# sensor.net
KiCad netlist of a schematic drawn in EAGLE
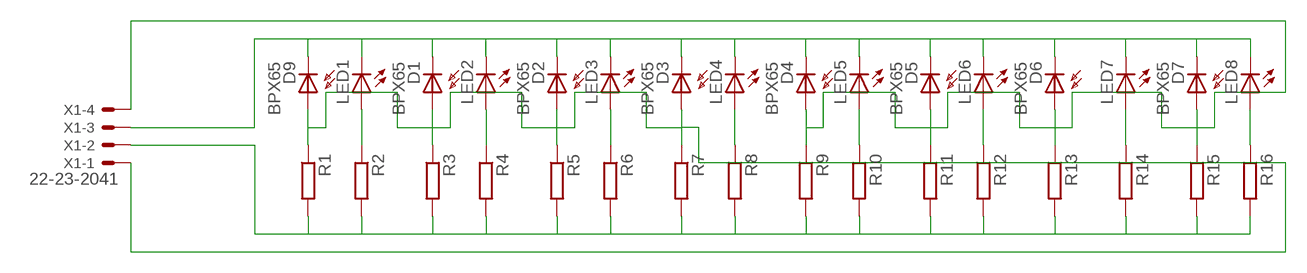
[diagram p0: schematic, sheet 1]

(export (version "E")
  (design (tool "Eeschema 10.0.6"))
  (components
    (comp (ref "D1")
      (value "BPX65")
      (footprint "eagle-import:BPX65")
      (fields
        (field (name "MPN") "BPX65.")
        (field (name "MPN_1") "BPX65.")
        (field (name "OC_FARNELL") "327451")
        (field (name "OC_NEWARK") "06WX2764")
      )
      (libsource (lib "eagle-import") (part "BPX65"))
    )
    (comp (ref "D2")
      (value "BPX65")
      (footprint "eagle-import:BPX65")
      (fields
        (field (name "MPN") "BPX65.")
        (field (name "MPN_1") "BPX65.")
        (field (name "OC_FARNELL") "327451")
        (field (name "OC_NEWARK") "06WX2764")
      )
      (libsource (lib "eagle-import") (part "BPX65"))
    )
    (comp (ref "D3")
      (value "BPX65")
      (footprint "eagle-import:BPX65")
      (fields
        (field (name "MPN") "BPX65.")
        (field (name "MPN_1") "BPX65.")
        (field (name "OC_FARNELL") "327451")
        (field (name "OC_NEWARK") "06WX2764")
      )
      (libsource (lib "eagle-import") (part "BPX65"))
    )
    (comp (ref "D4")
      (value "BPX65")
      (footprint "eagle-import:BPX65")
      (fields
        (field (name "MPN") "BPX65.")
        (field (name "MPN_1") "BPX65.")
        (field (name "OC_FARNELL") "327451")
        (field (name "OC_NEWARK") "06WX2764")
      )
      (libsource (lib "eagle-import") (part "BPX65"))
    )
    (comp (ref "D5")
      (value "BPX65")
      (footprint "eagle-import:BPX65")
      (fields
        (field (name "MPN") "BPX65.")
        (field (name "MPN_1") "BPX65.")
        (field (name "OC_FARNELL") "327451")
        (field (name "OC_NEWARK") "06WX2764")
      )
      (libsource (lib "eagle-import") (part "BPX65"))
    )
    (comp (ref "D6")
      (value "BPX65")
      (footprint "eagle-import:BPX65")
      (fields
        (field (name "MPN") "BPX65.")
        (field (name "MPN_1") "BPX65.")
        (field (name "OC_FARNELL") "327451")
        (field (name "OC_NEWARK") "06WX2764")
      )
      (libsource (lib "eagle-import") (part "BPX65"))
    )
    (comp (ref "D7")
      (value "BPX65")
      (footprint "eagle-import:BPX65")
      (fields
        (field (name "MPN") "BPX65.")
        (field (name "MPN_1") "BPX65.")
        (field (name "OC_FARNELL") "327451")
        (field (name "OC_NEWARK") "06WX2764")
      )
      (libsource (lib "eagle-import") (part "BPX65"))
    )
    (comp (ref "D9")
      (value "BPX65")
      (footprint "eagle-import:BPX65")
      (fields (field (name "MPN") "BPX65."))
      (libsource (lib "eagle-import") (part "BPX65"))
    )
    (comp (ref "LED1")
      (value "LED3MM")
      (footprint "eagle-import:LED3MM")
      (libsource (lib "eagle-import") (part "LED3MM"))
    )
    (comp (ref "LED2")
      (value "LED3MM")
      (footprint "eagle-import:LED3MM")
      (libsource (lib "eagle-import") (part "LED3MM"))
    )
    (comp (ref "LED3")
      (value "LED3MM")
      (footprint "eagle-import:LED3MM")
      (libsource (lib "eagle-import") (part "LED3MM"))
    )
    (comp (ref "LED4")
      (value "LED3MM")
      (footprint "eagle-import:LED3MM")
      (libsource (lib "eagle-import") (part "LED3MM"))
    )
    (comp (ref "LED5")
      (value "LED3MM")
      (footprint "eagle-import:LED3MM")
      (libsource (lib "eagle-import") (part "LED3MM"))
    )
    (comp (ref "LED6")
      (value "LED3MM")
      (footprint "eagle-import:LED3MM")
      (libsource (lib "eagle-import") (part "LED3MM"))
    )
    (comp (ref "LED7")
      (value "LED3MM")
      (footprint "eagle-import:LED3MM")
      (libsource (lib "eagle-import") (part "LED3MM"))
    )
    (comp (ref "LED8")
      (value "LED3MM")
      (footprint "eagle-import:LED3MM")
      (libsource (lib "eagle-import") (part "LED3MM"))
    )
    (comp (ref "R1")
      (value "R-EU_0204/7")
      (footprint "eagle-import:0204_7")
      (libsource (lib "eagle-import") (part "R-EU_0204/7"))
    )
    (comp (ref "R2")
      (value "R-EU_0204/7")
      (footprint "eagle-import:0204_7")
      (libsource (lib "eagle-import") (part "R-EU_0204/7"))
    )
    (comp (ref "R3")
      (value "R-EU_0204/7")
      (footprint "eagle-import:0204_7")
      (libsource (lib "eagle-import") (part "R-EU_0204/7"))
    )
    (comp (ref "R4")
      (value "R-EU_0204/7")
      (footprint "eagle-import:0204_7")
      (libsource (lib "eagle-import") (part "R-EU_0204/7"))
    )
    (comp (ref "R5")
      (value "R-EU_0204/7")
      (footprint "eagle-import:0204_7")
      (libsource (lib "eagle-import") (part "R-EU_0204/7"))
    )
    (comp (ref "R6")
      (value "R-EU_0204/7")
      (footprint "eagle-import:0204_7")
      (libsource (lib "eagle-import") (part "R-EU_0204/7"))
    )
    (comp (ref "R7")
      (value "R-EU_0204/7")
      (footprint "eagle-import:0204_7")
      (libsource (lib "eagle-import") (part "R-EU_0204/7"))
    )
    (comp (ref "R8")
      (value "R-EU_0204/7")
      (footprint "eagle-import:0204_7")
      (libsource (lib "eagle-import") (part "R-EU_0204/7"))
    )
    (comp (ref "R9")
      (value "R-EU_0204/7")
      (footprint "eagle-import:0204_7")
      (libsource (lib "eagle-import") (part "R-EU_0204/7"))
    )
    (comp (ref "R10")
      (value "R-EU_0204/7")
      (footprint "eagle-import:0204_7")
      (libsource (lib "eagle-import") (part "R-EU_0204/7"))
    )
    (comp (ref "R11")
      (value "R-EU_0204/7")
      (footprint "eagle-import:0204_7")
      (libsource (lib "eagle-import") (part "R-EU_0204/7"))
    )
    (comp (ref "R12")
      (value "R-EU_0204/7")
      (footprint "eagle-import:0204_7")
      (libsource (lib "eagle-import") (part "R-EU_0204/7"))
    )
    (comp (ref "R13")
      (value "R-EU_0204/7")
      (footprint "eagle-import:0204_7")
      (libsource (lib "eagle-import") (part "R-EU_0204/7"))
    )
    (comp (ref "R14")
      (value "R-EU_0204/7")
      (footprint "eagle-import:0204_7")
      (libsource (lib "eagle-import") (part "R-EU_0204/7"))
    )
    (comp (ref "R15")
      (value "R-EU_0204/7")
      (footprint "eagle-import:0204_7")
      (libsource (lib "eagle-import") (part "R-EU_0204/7"))
    )
    (comp (ref "R16")
      (value "R-EU_0204/7")
      (footprint "eagle-import:0204_7")
      (libsource (lib "eagle-import") (part "R-EU_0204/7"))
    )
    (comp (ref "X1")
      (value "22-23-2041")
      (footprint "eagle-import:22-23-2041")
      (fields (field (name "MF") "MOLEX"))
      (libsource (lib "eagle-import") (part "22-23-2041"))
    )
  )
  (nets
    (net (code "1") (name "Net-(D1-C)") (class "Default")
      (node (ref "D1") (pin "K") (pinfunction "C_K") (pintype "passive"))
      (node (ref "D2") (pin "K") (pinfunction "C_K") (pintype "passive"))
      (node (ref "D3") (pin "K") (pinfunction "C_K") (pintype "passive"))
      (node (ref "D4") (pin "K") (pinfunction "C_K") (pintype "passive"))
      (node (ref "D5") (pin "K") (pinfunction "C_K") (pintype "passive"))
      (node (ref "D6") (pin "K") (pinfunction "C_K") (pintype "passive"))
      (node (ref "D7") (pin "K") (pinfunction "C_K") (pintype "passive"))
      (node (ref "D9") (pin "K") (pinfunction "C_K") (pintype "passive"))
      (node (ref "LED1") (pin "K") (pinfunction "C_K") (pintype "passive"))
      (node (ref "LED2") (pin "K") (pinfunction "C_K") (pintype "passive"))
      (node (ref "LED3") (pin "K") (pinfunction "C_K") (pintype "passive"))
      (node (ref "LED4") (pin "K") (pinfunction "C_K") (pintype "passive"))
      (node (ref "LED5") (pin "K") (pinfunction "C_K") (pintype "passive"))
      (node (ref "LED6") (pin "K") (pinfunction "C_K") (pintype "passive"))
      (node (ref "LED7") (pin "K") (pinfunction "C_K") (pintype "passive"))
      (node (ref "LED8") (pin "K") (pinfunction "C_K") (pintype "passive"))
      (node (ref "X1") (pin "3") (pinfunction "S_3") (pintype "passive"))
    )
    (net (code "2") (name "Net-(LED1-PadA)") (class "Default")
      (node (ref "LED1") (pin "A") (pinfunction "A_A") (pintype "passive"))
      (node (ref "R2") (pin "1") (pinfunction "1_1") (pintype "passive"))
    )
    (net (code "3") (name "Net-(LED2-PadA)") (class "Default")
      (node (ref "LED2") (pin "A") (pinfunction "A_A") (pintype "passive"))
      (node (ref "R4") (pin "1") (pinfunction "1_1") (pintype "passive"))
    )
    (net (code "4") (name "Net-(LED3-PadA)") (class "Default")
      (node (ref "LED3") (pin "A") (pinfunction "A_A") (pintype "passive"))
      (node (ref "R6") (pin "1") (pinfunction "1_1") (pintype "passive"))
    )
    (net (code "5") (name "Net-(LED4-PadA)") (class "Default")
      (node (ref "LED4") (pin "A") (pinfunction "A_A") (pintype "passive"))
      (node (ref "R8") (pin "1") (pinfunction "1_1") (pintype "passive"))
    )
    (net (code "6") (name "Net-(LED5-PadA)") (class "Default")
      (node (ref "LED5") (pin "A") (pinfunction "A_A") (pintype "passive"))
      (node (ref "R10") (pin "1") (pinfunction "1_1") (pintype "passive"))
    )
    (net (code "7") (name "Net-(LED6-PadA)") (class "Default")
      (node (ref "LED6") (pin "A") (pinfunction "A_A") (pintype "passive"))
      (node (ref "R12") (pin "1") (pinfunction "1_1") (pintype "passive"))
    )
    (net (code "8") (name "Net-(LED7-PadA)") (class "Default")
      (node (ref "LED7") (pin "A") (pinfunction "A_A") (pintype "passive"))
      (node (ref "R14") (pin "1") (pinfunction "1_1") (pintype "passive"))
    )
    (net (code "9") (name "Net-(LED8-PadA)") (class "Default")
      (node (ref "LED8") (pin "A") (pinfunction "A_A") (pintype "passive"))
      (node (ref "R16") (pin "1") (pinfunction "1_1") (pintype "passive"))
    )
    (net (code "10") (name "Net-(X1A-S)") (class "Default")
      (node (ref "D1") (pin "A") (pinfunction "A_A") (pintype "passive"))
      (node (ref "D2") (pin "A") (pinfunction "A_A") (pintype "passive"))
      (node (ref "D3") (pin "A") (pinfunction "A_A") (pintype "passive"))
      (node (ref "D9") (pin "A") (pinfunction "A_A") (pintype "passive"))
      (node (ref "R1") (pin "1") (pinfunction "1_1") (pintype "passive"))
      (node (ref "R3") (pin "1") (pinfunction "1_1") (pintype "passive"))
      (node (ref "R5") (pin "1") (pinfunction "1_1") (pintype "passive"))
      (node (ref "R7") (pin "1") (pinfunction "1_1") (pintype "passive"))
      (node (ref "X1") (pin "1") (pinfunction "S_1") (pintype "passive"))
    )
    (net (code "11") (name "Net-(X1B-S)") (class "Default")
      (node (ref "R1") (pin "2") (pinfunction "2_2") (pintype "passive"))
      (node (ref "R10") (pin "2") (pinfunction "2_2") (pintype "passive"))
      (node (ref "R11") (pin "2") (pinfunction "2_2") (pintype "passive"))
      (node (ref "R12") (pin "2") (pinfunction "2_2") (pintype "passive"))
      (node (ref "R13") (pin "2") (pinfunction "2_2") (pintype "passive"))
      (node (ref "R14") (pin "2") (pinfunction "2_2") (pintype "passive"))
      (node (ref "R15") (pin "2") (pinfunction "2_2") (pintype "passive"))
      (node (ref "R16") (pin "2") (pinfunction "2_2") (pintype "passive"))
      (node (ref "R2") (pin "2") (pinfunction "2_2") (pintype "passive"))
      (node (ref "R3") (pin "2") (pinfunction "2_2") (pintype "passive"))
      (node (ref "R4") (pin "2") (pinfunction "2_2") (pintype "passive"))
      (node (ref "R5") (pin "2") (pinfunction "2_2") (pintype "passive"))
      (node (ref "R6") (pin "2") (pinfunction "2_2") (pintype "passive"))
      (node (ref "R7") (pin "2") (pinfunction "2_2") (pintype "passive"))
      (node (ref "R8") (pin "2") (pinfunction "2_2") (pintype "passive"))
      (node (ref "R9") (pin "2") (pinfunction "2_2") (pintype "passive"))
      (node (ref "X1") (pin "2") (pinfunction "S_2") (pintype "passive"))
    )
    (net (code "12") (name "Net-(X1D-S)") (class "Default")
      (node (ref "D4") (pin "A") (pinfunction "A_A") (pintype "passive"))
      (node (ref "D5") (pin "A") (pinfunction "A_A") (pintype "passive"))
      (node (ref "D6") (pin "A") (pinfunction "A_A") (pintype "passive"))
      (node (ref "D7") (pin "A") (pinfunction "A_A") (pintype "passive"))
      (node (ref "R11") (pin "1") (pinfunction "1_1") (pintype "passive"))
      (node (ref "R13") (pin "1") (pinfunction "1_1") (pintype "passive"))
      (node (ref "R15") (pin "1") (pinfunction "1_1") (pintype "passive"))
      (node (ref "R9") (pin "1") (pinfunction "1_1") (pintype "passive"))
      (node (ref "X1") (pin "4") (pinfunction "S_4") (pintype "passive"))
    )
  )
)
